# usb-current-meter.net
KiCad netlist of a schematic drawn in EAGLE
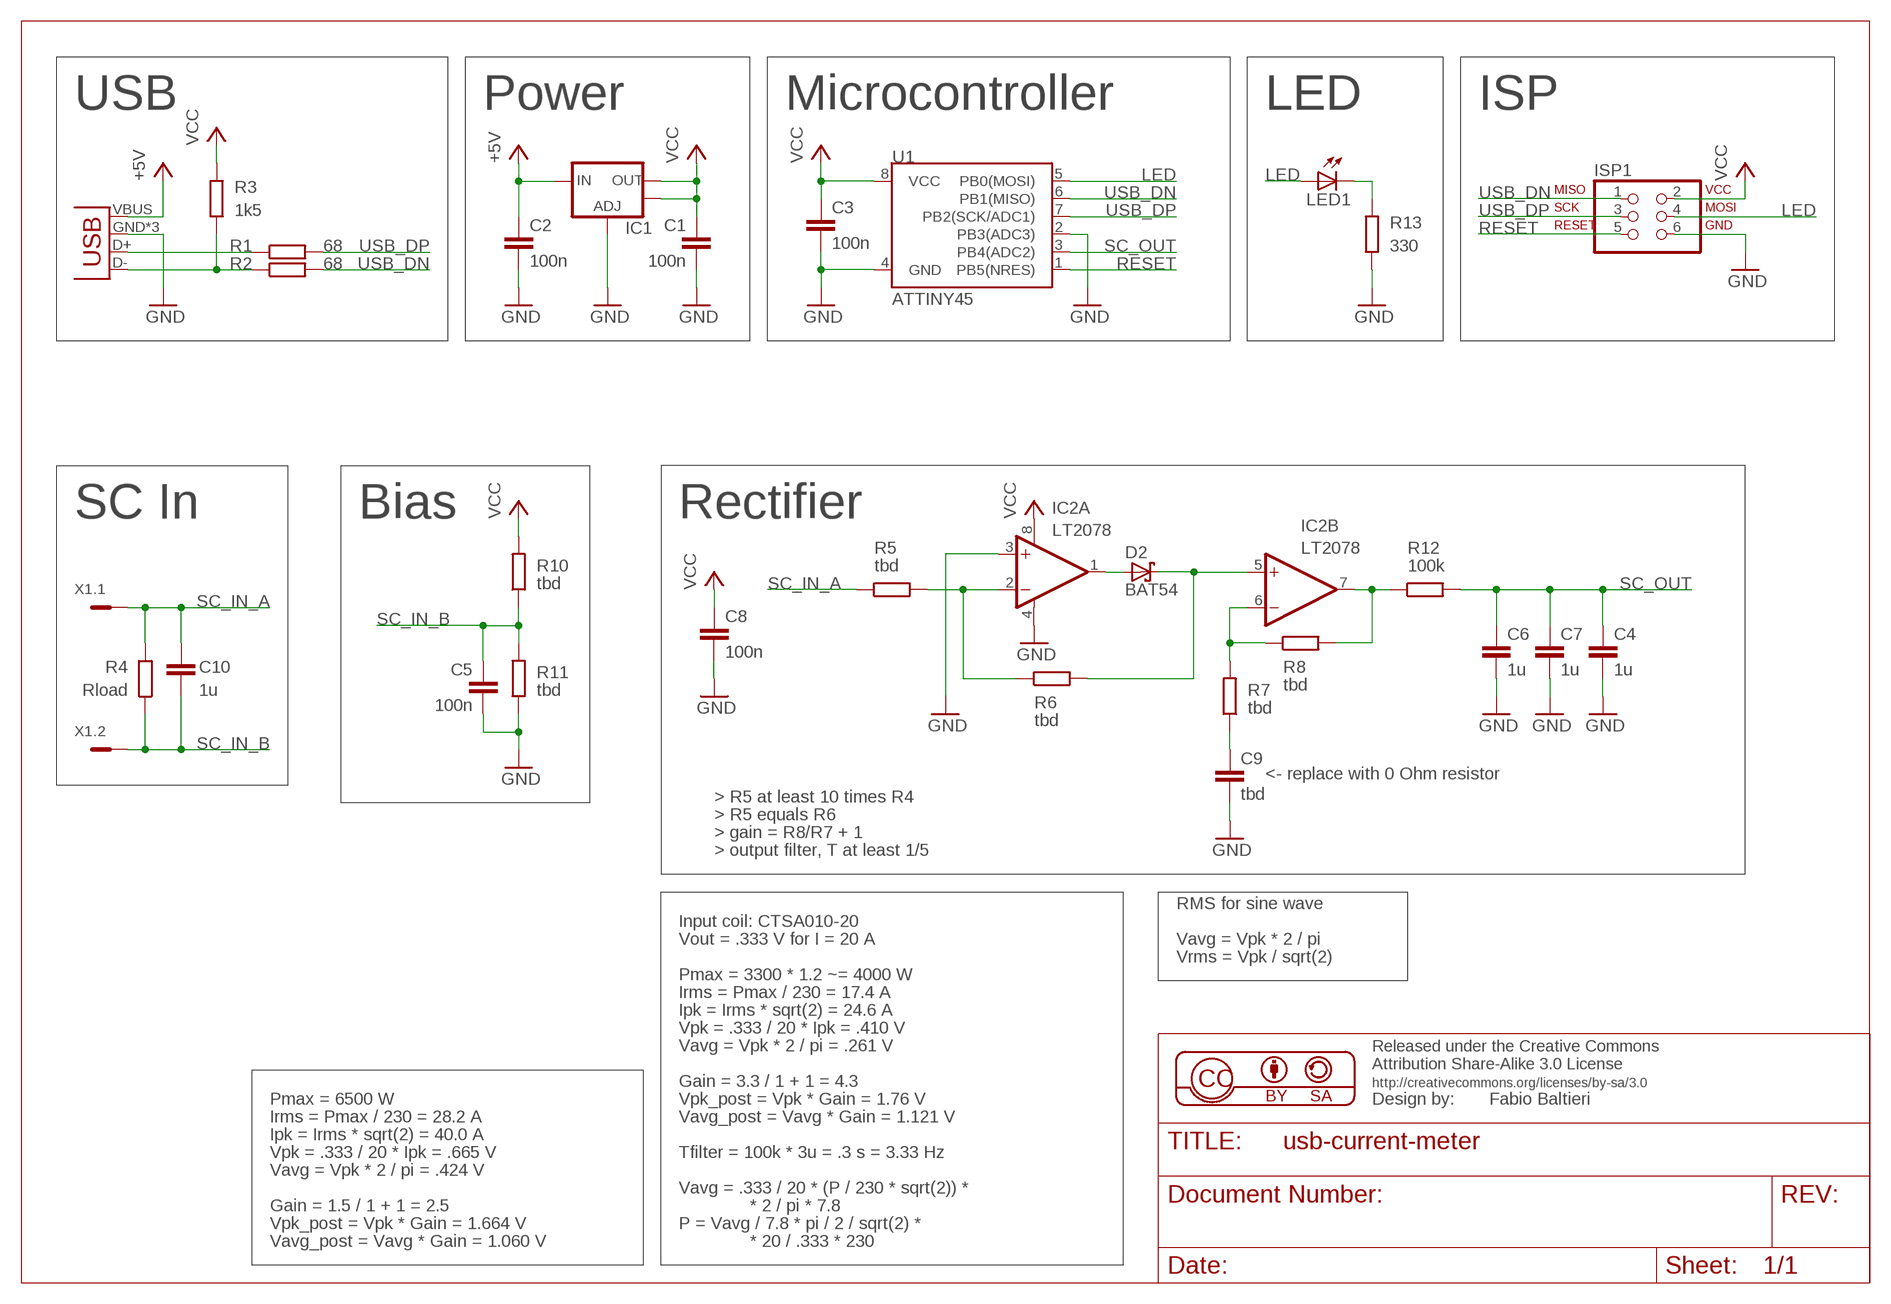
[diagram p0: schematic, sheet 1]

(export (version "E")
  (design (tool "Eeschema 10.0.6"))
  (components
    (comp (ref "C1")
      (value "100n")
      (footprint "eagle-import:C0805")
      (libsource (lib "eagle-import") (part "C-EUC0805"))
    )
    (comp (ref "C2")
      (value "100n")
      (footprint "eagle-import:C0805")
      (libsource (lib "eagle-import") (part "C-EUC0805"))
    )
    (comp (ref "C3")
      (value "100n")
      (footprint "eagle-import:C0805")
      (libsource (lib "eagle-import") (part "C-EUC0805"))
    )
    (comp (ref "C4")
      (value "1u")
      (footprint "eagle-import:C0805")
      (libsource (lib "eagle-import") (part "C-EUC0805"))
    )
    (comp (ref "C5")
      (value "100n")
      (footprint "eagle-import:C0805")
      (libsource (lib "eagle-import") (part "C-EUC0805"))
    )
    (comp (ref "C6")
      (value "1u")
      (footprint "eagle-import:C0805")
      (libsource (lib "eagle-import") (part "C-EUC0805"))
    )
    (comp (ref "C7")
      (value "1u")
      (footprint "eagle-import:C0805")
      (libsource (lib "eagle-import") (part "C-EUC0805"))
    )
    (comp (ref "C8")
      (value "100n")
      (footprint "eagle-import:C0805")
      (libsource (lib "eagle-import") (part "C-EUC0805"))
    )
    (comp (ref "C9")
      (value "tbd")
      (footprint "eagle-import:C0805")
      (libsource (lib "eagle-import") (part "C-EUC0805"))
    )
    (comp (ref "C10")
      (value "1u")
      (footprint "eagle-import:C0805")
      (libsource (lib "eagle-import") (part "C-EUC0805"))
    )
    (comp (ref "D2")
      (value "BAT54")
      (footprint "eagle-import:SOT23")
      (libsource (lib "eagle-import") (part "BAT54"))
    )
    (comp (ref "IC1")
      (value "V_REG_LM1117SOT223")
      (footprint "eagle-import:SOT223")
      (libsource (lib "eagle-import") (part "V_REG_LM1117SOT223"))
    )
    (comp (ref "IC2")
      (value "LT2078")
      (footprint "eagle-import:SO08")
      (fields (field (name "MF") "TEXAS INSTRUMENTS") (field (name "MPN") "OPA2234U"))
      (libsource (lib "eagle-import") (part "OPA2234U"))
    )
    (comp (ref "ISP1")
      (value "ISP-AVR910")
      (footprint "eagle-import:2X03_BORDER_TP")
      (libsource (lib "eagle-import") (part "ISP-AVR910"))
    )
    (comp (ref "LED1")
      (value "LEDSML0805")
      (footprint "eagle-import:SML0805")
      (libsource (lib "eagle-import") (part "LEDSML0805"))
    )
    (comp (ref "R1")
      (value "68")
      (footprint "eagle-import:R0603")
      (libsource (lib "eagle-import") (part "R-EU_R0603"))
    )
    (comp (ref "R2")
      (value "68")
      (footprint "eagle-import:R0603")
      (libsource (lib "eagle-import") (part "R-EU_R0603"))
    )
    (comp (ref "R3")
      (value "1k5")
      (footprint "eagle-import:R0603")
      (libsource (lib "eagle-import") (part "R-EU_R0603"))
    )
    (comp (ref "R4")
      (value "Rload")
      (footprint "eagle-import:R0805")
      (libsource (lib "eagle-import") (part "R-EU_R0805"))
    )
    (comp (ref "R5")
      (value "tbd")
      (footprint "eagle-import:R0603")
      (libsource (lib "eagle-import") (part "R-EU_R0603"))
    )
    (comp (ref "R6")
      (value "tbd")
      (footprint "eagle-import:R0603")
      (libsource (lib "eagle-import") (part "R-EU_R0603"))
    )
    (comp (ref "R7")
      (value "tbd")
      (footprint "eagle-import:R0603")
      (libsource (lib "eagle-import") (part "R-EU_R0603"))
    )
    (comp (ref "R8")
      (value "tbd")
      (footprint "eagle-import:R0603")
      (libsource (lib "eagle-import") (part "R-EU_R0603"))
    )
    (comp (ref "R10")
      (value "tbd")
      (footprint "eagle-import:R0603")
      (libsource (lib "eagle-import") (part "R-EU_R0603"))
    )
    (comp (ref "R11")
      (value "tbd")
      (footprint "eagle-import:R0603")
      (libsource (lib "eagle-import") (part "R-EU_R0603"))
    )
    (comp (ref "R12")
      (value "100k")
      (footprint "eagle-import:R0603")
      (libsource (lib "eagle-import") (part "R-EU_R0603"))
    )
    (comp (ref "R13")
      (value "330")
      (footprint "eagle-import:R0603")
      (libsource (lib "eagle-import") (part "R-EU_R0603"))
    )
    (comp (ref "U1")
      (value "ATTINY45")
      (footprint "eagle-import:SO08-EIAJ")
      (libsource (lib "eagle-import") (part "ATTINY45"))
    )
    (comp (ref "X1")
      (value "MC2")
      (footprint "eagle-import:MC2")
      (libsource (lib "eagle-import") (part "MC2"))
    )
    (comp (ref "X3")
      (value "USB-A-H")
      (footprint "eagle-import:USB-A-H")
      (libsource (lib "eagle-import") (part "USB-A-H"))
    )
  )
  (nets
    (net (code "1") (name "+5V") (class "Default")
      (node (ref "C2") (pin "1") (pinfunction "1_1") (pintype "passive"))
      (node (ref "IC1") (pin "3") (pinfunction "IN_3") (pintype "input"))
      (node (ref "X3") (pin "VBUS") (pinfunction "GND_VBUS") (pintype "bidirectional"))
    )
    (net (code "2") (name "/LED") (class "Default")
      (node (ref "ISP1") (pin "4") (pinfunction "4_4") (pintype "passive"))
      (node (ref "LED1") (pin "A") (pinfunction "A_A") (pintype "passive"))
      (node (ref "U1") (pin "5") (pinfunction "PB0(MOSI)_5") (pintype "bidirectional"))
    )
    (net (code "3") (name "/RESET") (class "Default")
      (node (ref "ISP1") (pin "5") (pinfunction "5_5") (pintype "passive"))
      (node (ref "U1") (pin "1") (pinfunction "PB5(NRES)_1") (pintype "bidirectional"))
    )
    (net (code "4") (name "/SC_IN_A") (class "Default")
      (node (ref "C10") (pin "1") (pinfunction "1_1") (pintype "passive"))
      (node (ref "R4") (pin "2") (pinfunction "2_2") (pintype "passive"))
      (node (ref "R5") (pin "1") (pinfunction "1_1") (pintype "passive"))
      (node (ref "X1") (pin "1") (pinfunction "SK_1") (pintype "passive"))
    )
    (net (code "5") (name "/SC_IN_B") (class "Default")
      (node (ref "C10") (pin "2") (pinfunction "2_2") (pintype "passive"))
      (node (ref "C5") (pin "1") (pinfunction "1_1") (pintype "passive"))
      (node (ref "R10") (pin "1") (pinfunction "1_1") (pintype "passive"))
      (node (ref "R11") (pin "2") (pinfunction "2_2") (pintype "passive"))
      (node (ref "R4") (pin "1") (pinfunction "1_1") (pintype "passive"))
      (node (ref "X1") (pin "2") (pinfunction "SK_2") (pintype "passive"))
    )
    (net (code "6") (name "/SC_OUT") (class "Default")
      (node (ref "C4") (pin "1") (pinfunction "1_1") (pintype "passive"))
      (node (ref "C6") (pin "1") (pinfunction "1_1") (pintype "passive"))
      (node (ref "C7") (pin "1") (pinfunction "1_1") (pintype "passive"))
      (node (ref "R12") (pin "2") (pinfunction "2_2") (pintype "passive"))
      (node (ref "U1") (pin "3") (pinfunction "PB4(ADC2)_3") (pintype "bidirectional"))
    )
    (net (code "7") (name "/USB_DN") (class "Default")
      (node (ref "ISP1") (pin "1") (pinfunction "1_1") (pintype "passive"))
      (node (ref "R2") (pin "2") (pinfunction "2_2") (pintype "passive"))
      (node (ref "U1") (pin "6") (pinfunction "PB1(MISO)_6") (pintype "bidirectional"))
    )
    (net (code "8") (name "/USB_DP") (class "Default")
      (node (ref "ISP1") (pin "3") (pinfunction "3_3") (pintype "passive"))
      (node (ref "R1") (pin "2") (pinfunction "2_2") (pintype "passive"))
      (node (ref "U1") (pin "7") (pinfunction "PB2(SCK/ADC1)_7") (pintype "bidirectional"))
    )
    (net (code "9") (name "GND") (class "Default")
      (node (ref "C1") (pin "2") (pinfunction "2_2") (pintype "passive"))
      (node (ref "C2") (pin "2") (pinfunction "2_2") (pintype "passive"))
      (node (ref "C3") (pin "2") (pinfunction "2_2") (pintype "passive"))
      (node (ref "C4") (pin "2") (pinfunction "2_2") (pintype "passive"))
      (node (ref "C5") (pin "2") (pinfunction "2_2") (pintype "passive"))
      (node (ref "C6") (pin "2") (pinfunction "2_2") (pintype "passive"))
      (node (ref "C7") (pin "2") (pinfunction "2_2") (pintype "passive"))
      (node (ref "C8") (pin "2") (pinfunction "2_2") (pintype "passive"))
      (node (ref "C9") (pin "2") (pinfunction "2_2") (pintype "passive"))
      (node (ref "IC1") (pin "1") (pinfunction "ADJ_1") (pintype "input"))
      (node (ref "IC2") (pin "3") (pinfunction "+IN_3") (pintype "input"))
      (node (ref "IC2") (pin "4") (pinfunction "V-_4") (pintype "power_in"))
      (node (ref "ISP1") (pin "6") (pinfunction "6_6") (pintype "passive"))
      (node (ref "R11") (pin "1") (pinfunction "1_1") (pintype "passive"))
      (node (ref "R13") (pin "1") (pinfunction "1_1") (pintype "passive"))
      (node (ref "U1") (pin "2") (pinfunction "PB3(ADC3)_2") (pintype "bidirectional"))
      (node (ref "U1") (pin "4") (pinfunction "GND_4") (pintype "bidirectional"))
      (node (ref "X3") (pin "GND") (pinfunction "VBUS_GND") (pintype "bidirectional"))
      (node (ref "X3") (pin "GND2") (pinfunction "VBUS_GND2") (pintype "bidirectional"))
      (node (ref "X3") (pin "GND3") (pinfunction "VBUS_GND3") (pintype "bidirectional"))
    )
    (net (code "10") (name "Net-(C9-Pad1)") (class "Default")
      (node (ref "C9") (pin "1") (pinfunction "1_1") (pintype "passive"))
      (node (ref "R7") (pin "1") (pinfunction "1_1") (pintype "passive"))
    )
    (net (code "11") (name "Net-(D2-A)") (class "Default")
      (node (ref "D2") (pin "1") (pinfunction "A_1") (pintype "passive"))
      (node (ref "IC2") (pin "1") (pinfunction "OUT_1") (pintype "output"))
    )
    (net (code "12") (name "Net-(D2-C)") (class "Default")
      (node (ref "D2") (pin "3") (pinfunction "C_3") (pintype "passive"))
      (node (ref "IC2") (pin "5") (pinfunction "+IN_5") (pintype "input"))
      (node (ref "R6") (pin "2") (pinfunction "2_2") (pintype "passive"))
    )
    (net (code "13") (name "Net-(IC2A--IN)") (class "Default")
      (node (ref "IC2") (pin "2") (pinfunction "-IN_2") (pintype "input"))
      (node (ref "R5") (pin "2") (pinfunction "2_2") (pintype "passive"))
      (node (ref "R6") (pin "1") (pinfunction "1_1") (pintype "passive"))
    )
    (net (code "14") (name "Net-(IC2B--IN)") (class "Default")
      (node (ref "IC2") (pin "6") (pinfunction "-IN_6") (pintype "input"))
      (node (ref "R7") (pin "2") (pinfunction "2_2") (pintype "passive"))
      (node (ref "R8") (pin "1") (pinfunction "1_1") (pintype "passive"))
    )
    (net (code "15") (name "Net-(IC2B-OUT)") (class "Default")
      (node (ref "IC2") (pin "7") (pinfunction "OUT_7") (pintype "output"))
      (node (ref "R12") (pin "1") (pinfunction "1_1") (pintype "passive"))
      (node (ref "R8") (pin "2") (pinfunction "2_2") (pintype "passive"))
    )
    (net (code "16") (name "Net-(LED1-PadC)") (class "Default")
      (node (ref "LED1") (pin "C") (pinfunction "C_C") (pintype "passive"))
      (node (ref "R13") (pin "2") (pinfunction "2_2") (pintype "passive"))
    )
    (net (code "17") (name "Net-(X3-D+)") (class "Default")
      (node (ref "R2") (pin "1") (pinfunction "1_1") (pintype "passive"))
      (node (ref "R3") (pin "1") (pinfunction "1_1") (pintype "passive"))
      (node (ref "X3") (pin "D-") (pinfunction "D+_D-") (pintype "bidirectional"))
    )
    (net (code "18") (name "Net-(X3-D-)") (class "Default")
      (node (ref "R1") (pin "1") (pinfunction "1_1") (pintype "passive"))
      (node (ref "X3") (pin "D+") (pinfunction "D-_D+") (pintype "bidirectional"))
    )
    (net (code "19") (name "VCC") (class "Default")
      (node (ref "C1") (pin "1") (pinfunction "1_1") (pintype "passive"))
      (node (ref "C3") (pin "1") (pinfunction "1_1") (pintype "passive"))
      (node (ref "C8") (pin "1") (pinfunction "1_1") (pintype "passive"))
      (node (ref "IC1") (pin "2") (pinfunction "OUT_2") (pintype "output"))
      (node (ref "IC1") (pin "4") (pinfunction "OUT_4") (pintype "output"))
      (node (ref "IC2") (pin "8") (pinfunction "V+_8") (pintype "power_in"))
      (node (ref "ISP1") (pin "2") (pinfunction "2_2") (pintype "passive"))
      (node (ref "R10") (pin "2") (pinfunction "2_2") (pintype "passive"))
      (node (ref "R3") (pin "2") (pinfunction "2_2") (pintype "passive"))
      (node (ref "U1") (pin "8") (pinfunction "VCC_8") (pintype "bidirectional"))
    )
  )
)
